# ab-main-mini.net
KiCad netlist of a schematic drawn in EAGLE
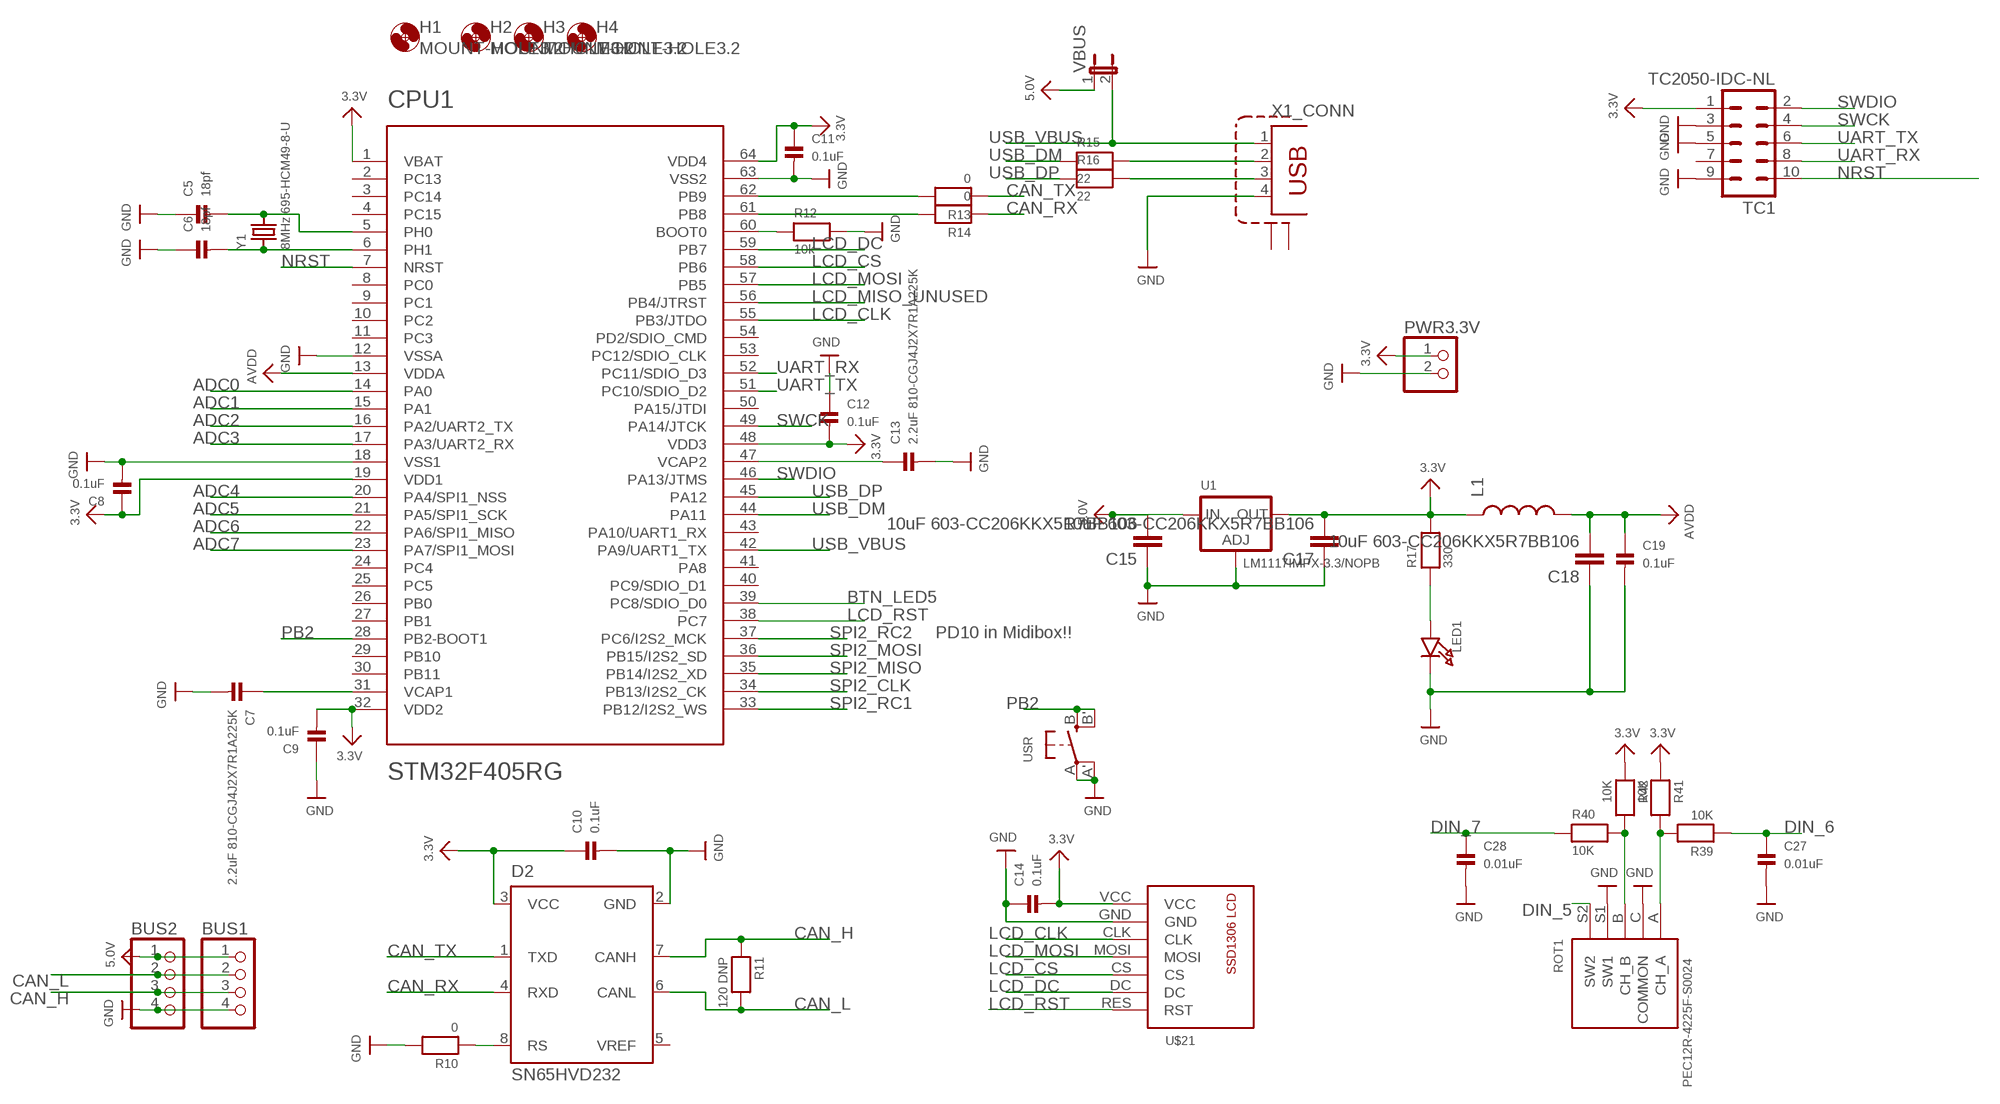
[diagram p0: schematic, sheet 1]

(export (version "E")
  (design (tool "Eeschema 10.0.6"))
  (components
    (comp (ref "BUS1")
      (value "HEADER-1X4ROUND")
      (footprint "eagle-import:1X04_ROUND")
      (libsource (lib "eagle-import") (part "HEADER-1X4ROUND"))
    )
    (comp (ref "BUS2")
      (value "HEADER-1X4ROUND")
      (footprint "eagle-import:1X04_ROUND")
      (libsource (lib "eagle-import") (part "HEADER-1X4ROUND"))
    )
    (comp (ref "C5")
      (value "18pf")
      (footprint "eagle-import:0603")
      (libsource (lib "eagle-import") (part "CAP_CERAMIC0603"))
    )
    (comp (ref "C6")
      (value "18pf")
      (footprint "eagle-import:0603")
      (libsource (lib "eagle-import") (part "CAP_CERAMIC0603"))
    )
    (comp (ref "C7")
      (value "2.2uF 810-CGJ4J2X7R1A225K")
      (footprint "eagle-import:0805")
      (libsource (lib "eagle-import") (part "CAP_CERAMIC0805"))
    )
    (comp (ref "C8")
      (value "0.1uF")
      (footprint "eagle-import:0603")
      (libsource (lib "eagle-import") (part "CAP_CERAMIC0603"))
    )
    (comp (ref "C9")
      (value "0.1uF")
      (footprint "eagle-import:0603")
      (libsource (lib "eagle-import") (part "CAP_CERAMIC0603"))
    )
    (comp (ref "C10")
      (value "0.1uF")
      (footprint "eagle-import:0603")
      (libsource (lib "eagle-import") (part "CAP_CERAMIC0603"))
    )
    (comp (ref "C11")
      (value "0.1uF")
      (footprint "eagle-import:0603")
      (libsource (lib "eagle-import") (part "CAP_CERAMIC0603"))
    )
    (comp (ref "C12")
      (value "0.1uF")
      (footprint "eagle-import:0603")
      (libsource (lib "eagle-import") (part "CAP_CERAMIC0603"))
    )
    (comp (ref "C13")
      (value "2.2uF 810-CGJ4J2X7R1A225K")
      (footprint "eagle-import:0805")
      (libsource (lib "eagle-import") (part "CAP_CERAMIC0805"))
    )
    (comp (ref "C14")
      (value "0.1uF")
      (footprint "eagle-import:0603")
      (libsource (lib "eagle-import") (part "CAP_CERAMIC0603"))
    )
    (comp (ref "C15")
      (value "10uF 603-CC206KKX5R7BB106")
      (footprint "eagle-import:1206")
      (libsource (lib "eagle-import") (part "CAP1206"))
    )
    (comp (ref "C17")
      (value "10uF 603-CC206KKX5R7BB106")
      (footprint "eagle-import:1206")
      (libsource (lib "eagle-import") (part "CAP1206"))
    )
    (comp (ref "C18")
      (value "10uF 603-CC206KKX5R7BB106")
      (footprint "eagle-import:1206")
      (libsource (lib "eagle-import") (part "CAP1206"))
    )
    (comp (ref "C19")
      (value "0.1uF")
      (footprint "eagle-import:0603")
      (libsource (lib "eagle-import") (part "CAP_CERAMIC0603"))
    )
    (comp (ref "C27")
      (value "0.01uF")
      (footprint "eagle-import:0603")
      (libsource (lib "eagle-import") (part "CAP_CERAMIC0603"))
    )
    (comp (ref "C28")
      (value "0.01uF")
      (footprint "eagle-import:0603")
      (libsource (lib "eagle-import") (part "CAP_CERAMIC0603"))
    )
    (comp (ref "CPU1")
      (value "STM32F405RG")
      (footprint "eagle-import:TQFP64")
      (libsource (lib "eagle-import") (part "STM32F405RG"))
    )
    (comp (ref "D2")
      (value "SN65HVD232")
      (footprint "eagle-import:SO8")
      (libsource (lib "eagle-import") (part "SN65HVD230"))
    )
    (comp (ref "H1")
      (value "MOUNT-HOLE3.2")
      (footprint "eagle-import:3,2")
      (libsource (lib "eagle-import") (part "MOUNT-HOLE3.2"))
    )
    (comp (ref "H2")
      (value "MOUNT-HOLE3.2")
      (footprint "eagle-import:3,2")
      (libsource (lib "eagle-import") (part "MOUNT-HOLE3.2"))
    )
    (comp (ref "H3")
      (value "MOUNT-HOLE3.2")
      (footprint "eagle-import:3,2")
      (libsource (lib "eagle-import") (part "MOUNT-HOLE3.2"))
    )
    (comp (ref "H4")
      (value "MOUNT-HOLE3.2")
      (footprint "eagle-import:3,2")
      (libsource (lib "eagle-import") (part "MOUNT-HOLE3.2"))
    )
    (comp (ref "L1")
      (value "INDUCTOR0805")
      (footprint "eagle-import:0805")
      (libsource (lib "eagle-import") (part "INDUCTOR0805"))
    )
    (comp (ref "LED1")
      (value "LED0603")
      (footprint "eagle-import:CHIPLED_0603")
      (libsource (lib "eagle-import") (part "LED0603"))
    )
    (comp (ref "PWR3.3V")
      (value "HEADER-1X2ROUND")
      (footprint "eagle-import:1X02_ROUND")
      (libsource (lib "eagle-import") (part "HEADER-1X2ROUND"))
    )
    (comp (ref "R10")
      (value "0")
      (footprint "eagle-import:_0603")
      (libsource (lib "eagle-import") (part "RESISTOR_0603"))
    )
    (comp (ref "R11")
      (value "120 DNP")
      (footprint "eagle-import:_0603")
      (libsource (lib "eagle-import") (part "RESISTOR_0603"))
    )
    (comp (ref "R12")
      (value "10k")
      (footprint "eagle-import:_0603")
      (libsource (lib "eagle-import") (part "RESISTOR_0603"))
    )
    (comp (ref "R13")
      (value "0")
      (footprint "eagle-import:_0603")
      (libsource (lib "eagle-import") (part "RESISTOR_0603"))
    )
    (comp (ref "R14")
      (value "0")
      (footprint "eagle-import:_0603")
      (libsource (lib "eagle-import") (part "RESISTOR_0603"))
    )
    (comp (ref "R15")
      (value "22")
      (footprint "eagle-import:0603")
      (libsource (lib "eagle-import") (part "RESISTOR0603"))
    )
    (comp (ref "R16")
      (value "22")
      (footprint "eagle-import:0603")
      (libsource (lib "eagle-import") (part "RESISTOR0603"))
    )
    (comp (ref "R17")
      (value "330")
      (footprint "eagle-import:0603")
      (libsource (lib "eagle-import") (part "RESISTOR0603"))
    )
    (comp (ref "R39")
      (value "10K")
      (footprint "eagle-import:0603")
      (libsource (lib "eagle-import") (part "RESISTOR0603"))
    )
    (comp (ref "R40")
      (value "10K")
      (footprint "eagle-import:0603")
      (libsource (lib "eagle-import") (part "RESISTOR0603"))
    )
    (comp (ref "R41")
      (value "10K")
      (footprint "eagle-import:0603")
      (libsource (lib "eagle-import") (part "RESISTOR0603"))
    )
    (comp (ref "R42")
      (value "10K")
      (footprint "eagle-import:0603")
      (libsource (lib "eagle-import") (part "RESISTOR0603"))
    )
    (comp (ref "ROT1")
      (value "PEC12R-4225F-S0024")
      (footprint "eagle-import:PEC111-4XXXK-SXXXX")
      (libsource (lib "eagle-import") (part "PEC11-4215K-S0024"))
    )
    (comp (ref "TC1")
      (value "TC2050-IDC-NL")
      (footprint "eagle-import:TC2050-IDC-NL")
      (libsource (lib "eagle-import") (part "TC2050-IDC-NL"))
    )
    (comp (ref "U$21")
      (value "SSD1306-7PIN")
      (footprint "eagle-import:SSD1306-7PIN")
      (libsource (lib "eagle-import") (part "SSD1306-7PIN"))
    )
    (comp (ref "U1")
      (value "LM1117IMPX-3.3/NOPB")
      (footprint "eagle-import:SOT223-R")
      (libsource (lib "eagle-import") (part "LM1117SOT223-REFLOW"))
    )
    (comp (ref "USR")
      (value "SWITCH_TACT_SMT")
      (footprint "eagle-import:EVQ-Q2")
      (libsource (lib "eagle-import") (part "SWITCH_TACT_SMT"))
    )
    (comp (ref "VBUS")
      (value "JUMPER2")
      (footprint "eagle-import:JUMPER2")
      (libsource (lib "eagle-import") (part "JUMPER2"))
    )
    (comp (ref "X1")
      (value "TE-292304-1")
      (footprint "eagle-import:TE-292304-1")
      (libsource (lib "eagle-import") (part "TE-292304-1"))
    )
    (comp (ref "Y1")
      (value "8MHz 695-HCM49-8-U")
      (footprint "eagle-import:HC49UP")
      (libsource (lib "eagle-import") (part "CRYSTALSMD"))
    )
  )
  (nets
    (net (code "1") (name "/ADC0") (class "Default")
      (node (ref "CPU1") (pin "14") (pinfunction "PA0_14") (pintype "bidirectional"))
    )
    (net (code "2") (name "/ADC1") (class "Default")
      (node (ref "CPU1") (pin "15") (pinfunction "PA1_15") (pintype "bidirectional"))
    )
    (net (code "3") (name "/ADC2") (class "Default")
      (node (ref "CPU1") (pin "16") (pinfunction "PA2/UART2_TX_16") (pintype "bidirectional"))
    )
    (net (code "4") (name "/ADC3") (class "Default")
      (node (ref "CPU1") (pin "17") (pinfunction "PA3/UART2_RX_17") (pintype "bidirectional"))
    )
    (net (code "5") (name "/ADC4") (class "Default")
      (node (ref "CPU1") (pin "20") (pinfunction "PA4/SPI1_NSS_20") (pintype "bidirectional"))
    )
    (net (code "6") (name "/ADC5") (class "Default")
      (node (ref "CPU1") (pin "21") (pinfunction "PA5/SPI1_SCK_21") (pintype "bidirectional"))
    )
    (net (code "7") (name "/ADC6") (class "Default")
      (node (ref "CPU1") (pin "22") (pinfunction "PA6/SPI1_MISO_22") (pintype "bidirectional"))
    )
    (net (code "8") (name "/ADC7") (class "Default")
      (node (ref "CPU1") (pin "23") (pinfunction "PA7/SPI1_MOSI_23") (pintype "bidirectional"))
    )
    (net (code "9") (name "/BTN_LED5") (class "Default")
      (node (ref "CPU1") (pin "39") (pinfunction "PC8/SDIO_D0_39") (pintype "bidirectional"))
    )
    (net (code "10") (name "/CAN_H") (class "Default")
      (node (ref "BUS1") (pin "3") (pinfunction "3_3") (pintype "passive"))
      (node (ref "BUS2") (pin "3") (pinfunction "3_3") (pintype "passive"))
      (node (ref "D2") (pin "7") (pinfunction "CANH_7") (pintype "bidirectional"))
      (node (ref "R11") (pin "1") (pinfunction "1_1") (pintype "passive"))
    )
    (net (code "11") (name "/CAN_L") (class "Default")
      (node (ref "BUS1") (pin "2") (pinfunction "2_2") (pintype "passive"))
      (node (ref "BUS2") (pin "2") (pinfunction "2_2") (pintype "passive"))
      (node (ref "D2") (pin "6") (pinfunction "CANL_6") (pintype "bidirectional"))
      (node (ref "R11") (pin "2") (pinfunction "2_2") (pintype "passive"))
    )
    (net (code "12") (name "/CAN_RX") (class "Default")
      (node (ref "D2") (pin "4") (pinfunction "RXD_4") (pintype "output"))
      (node (ref "R14") (pin "1") (pinfunction "1_1") (pintype "passive"))
    )
    (net (code "13") (name "/CAN_TX") (class "Default")
      (node (ref "D2") (pin "1") (pinfunction "TXD_1") (pintype "input"))
      (node (ref "R13") (pin "1") (pinfunction "1_1") (pintype "passive"))
    )
    (net (code "14") (name "/DIN_5") (class "Default")
      (node (ref "ROT1") (pin "S2") (pinfunction "SW2_S2") (pintype "bidirectional"))
    )
    (net (code "15") (name "/DIN_6") (class "Default")
      (node (ref "C27") (pin "1") (pinfunction "P$1_1") (pintype "passive"))
      (node (ref "R39") (pin "1") (pinfunction "1_1") (pintype "passive"))
    )
    (net (code "16") (name "/DIN_7") (class "Default")
      (node (ref "C28") (pin "1") (pinfunction "P$1_1") (pintype "passive"))
      (node (ref "R40") (pin "1") (pinfunction "1_1") (pintype "passive"))
    )
    (net (code "17") (name "/LCD_CLK") (class "Default")
      (node (ref "CPU1") (pin "55") (pinfunction "PB3/JTDO_55") (pintype "bidirectional"))
      (node (ref "U$21") (pin "CLK") (pinfunction "CLK_CLK") (pintype "bidirectional"))
    )
    (net (code "18") (name "/LCD_CS") (class "Default")
      (node (ref "CPU1") (pin "58") (pinfunction "PB6_58") (pintype "bidirectional"))
      (node (ref "U$21") (pin "CS") (pinfunction "CS_CS") (pintype "bidirectional"))
    )
    (net (code "19") (name "/LCD_DC") (class "Default")
      (node (ref "CPU1") (pin "59") (pinfunction "PB7_59") (pintype "bidirectional"))
      (node (ref "U$21") (pin "DC") (pinfunction "DC_DC") (pintype "bidirectional"))
    )
    (net (code "20") (name "/LCD_MISO_UNUSED") (class "Default")
      (node (ref "CPU1") (pin "56") (pinfunction "PB4/JTRST_56") (pintype "bidirectional"))
    )
    (net (code "21") (name "/LCD_MOSI") (class "Default")
      (node (ref "CPU1") (pin "57") (pinfunction "PB5_57") (pintype "bidirectional"))
      (node (ref "U$21") (pin "MOSI") (pinfunction "MOSI_MOSI") (pintype "bidirectional"))
    )
    (net (code "22") (name "/LCD_RST") (class "Default")
      (node (ref "CPU1") (pin "38") (pinfunction "PC7_38") (pintype "bidirectional"))
      (node (ref "U$21") (pin "RES") (pinfunction "RST_RES") (pintype "bidirectional"))
    )
    (net (code "23") (name "/NRST") (class "Default")
      (node (ref "CPU1") (pin "7") (pinfunction "NRST_7") (pintype "bidirectional"))
      (node (ref "TC1") (pin "10") (pinfunction "10_10") (pintype "passive"))
    )
    (net (code "24") (name "/PB2") (class "Default")
      (node (ref "CPU1") (pin "28") (pinfunction "PB2-BOOT1_28") (pintype "bidirectional"))
      (node (ref "USR") (pin "B") (pinfunction "S_B") (pintype "passive"))
      (node (ref "USR") (pin "B'") (pinfunction "S1_B'") (pintype "passive"))
    )
    (net (code "25") (name "/SPI2_CLK") (class "Default")
      (node (ref "CPU1") (pin "34") (pinfunction "PB13/I2S2_CK_34") (pintype "bidirectional"))
    )
    (net (code "26") (name "/SPI2_MISO") (class "Default")
      (node (ref "CPU1") (pin "35") (pinfunction "PB14/I2S2_XD_35") (pintype "bidirectional"))
    )
    (net (code "27") (name "/SPI2_MOSI") (class "Default")
      (node (ref "CPU1") (pin "36") (pinfunction "PB15/I2S2_SD_36") (pintype "bidirectional"))
    )
    (net (code "28") (name "/SPI2_RC1") (class "Default")
      (node (ref "CPU1") (pin "33") (pinfunction "PB12/I2S2_WS_33") (pintype "bidirectional"))
    )
    (net (code "29") (name "/SPI2_RC2") (class "Default")
      (node (ref "CPU1") (pin "37") (pinfunction "PC6/I2S2_MCK_37") (pintype "bidirectional"))
    )
    (net (code "30") (name "/SWCK") (class "Default")
      (node (ref "CPU1") (pin "49") (pinfunction "PA14/JTCK_49") (pintype "bidirectional"))
      (node (ref "TC1") (pin "4") (pinfunction "4_4") (pintype "passive"))
    )
    (net (code "31") (name "/SWDIO") (class "Default")
      (node (ref "CPU1") (pin "46") (pinfunction "PA13/JTMS_46") (pintype "bidirectional"))
      (node (ref "TC1") (pin "2") (pinfunction "2_2") (pintype "passive"))
    )
    (net (code "32") (name "/UART_RX") (class "Default")
      (node (ref "CPU1") (pin "52") (pinfunction "PC11/SDIO_D3_52") (pintype "bidirectional"))
      (node (ref "TC1") (pin "8") (pinfunction "8_8") (pintype "passive"))
    )
    (net (code "33") (name "/UART_TX") (class "Default")
      (node (ref "CPU1") (pin "51") (pinfunction "PC10/SDIO_D2_51") (pintype "bidirectional"))
      (node (ref "TC1") (pin "6") (pinfunction "6_6") (pintype "passive"))
    )
    (net (code "34") (name "/USB_DM") (class "Default")
      (node (ref "CPU1") (pin "44") (pinfunction "PA11_44") (pintype "bidirectional"))
      (node (ref "R15") (pin "1") (pinfunction "1_1") (pintype "passive"))
    )
    (net (code "35") (name "/USB_DP") (class "Default")
      (node (ref "CPU1") (pin "45") (pinfunction "PA12_45") (pintype "bidirectional"))
      (node (ref "R16") (pin "1") (pinfunction "1_1") (pintype "passive"))
    )
    (net (code "36") (name "/USB_VBUS") (class "Default")
      (node (ref "CPU1") (pin "42") (pinfunction "PA9/UART1_TX_42") (pintype "bidirectional"))
      (node (ref "VBUS") (pin "2") (pinfunction "2_2") (pintype "passive"))
      (node (ref "X1") (pin "1") (pinfunction "1_1") (pintype "bidirectional"))
    )
    (net (code "37") (name "3.3V") (class "Default")
      (node (ref "C10") (pin "1") (pinfunction "P$1_1") (pintype "passive"))
      (node (ref "C11") (pin "1") (pinfunction "P$1_1") (pintype "passive"))
      (node (ref "C12") (pin "2") (pinfunction "P$2_2") (pintype "passive"))
      (node (ref "C14") (pin "2") (pinfunction "P$2_2") (pintype "passive"))
      (node (ref "C17") (pin "2") (pinfunction "2_2") (pintype "passive"))
      (node (ref "C8") (pin "1") (pinfunction "P$1_1") (pintype "passive"))
      (node (ref "C9") (pin "2") (pinfunction "P$2_2") (pintype "passive"))
      (node (ref "CPU1") (pin "1") (pinfunction "VBAT_1") (pintype "bidirectional"))
      (node (ref "CPU1") (pin "19") (pinfunction "VDD1_19") (pintype "bidirectional"))
      (node (ref "CPU1") (pin "32") (pinfunction "VDD2_32") (pintype "bidirectional"))
      (node (ref "CPU1") (pin "48") (pinfunction "VDD3_48") (pintype "bidirectional"))
      (node (ref "CPU1") (pin "64") (pinfunction "VDD4_64") (pintype "bidirectional"))
      (node (ref "D2") (pin "3") (pinfunction "VCC_3") (pintype "power_in"))
      (node (ref "L1") (pin "1") (pinfunction "1_1") (pintype "passive"))
      (node (ref "PWR3.3V") (pin "1") (pinfunction "1_1") (pintype "passive"))
      (node (ref "R17") (pin "2") (pinfunction "2_2") (pintype "passive"))
      (node (ref "R41") (pin "1") (pinfunction "1_1") (pintype "passive"))
      (node (ref "R42") (pin "1") (pinfunction "1_1") (pintype "passive"))
      (node (ref "TC1") (pin "1") (pinfunction "1_1") (pintype "passive"))
      (node (ref "U$21") (pin "VCC") (pinfunction "VCC_VCC") (pintype "bidirectional"))
      (node (ref "U1") (pin "2") (pinfunction "OUT_2") (pintype "passive"))
    )
    (net (code "38") (name "5.0V") (class "Default")
      (node (ref "BUS1") (pin "1") (pinfunction "1_1") (pintype "passive"))
      (node (ref "BUS2") (pin "1") (pinfunction "1_1") (pintype "passive"))
      (node (ref "C15") (pin "2") (pinfunction "2_2") (pintype "passive"))
      (node (ref "U1") (pin "3") (pinfunction "IN_3") (pintype "input"))
      (node (ref "VBUS") (pin "1") (pinfunction "1_1") (pintype "passive"))
    )
    (net (code "39") (name "AVDD") (class "Default")
      (node (ref "C18") (pin "2") (pinfunction "2_2") (pintype "passive"))
      (node (ref "C19") (pin "1") (pinfunction "P$1_1") (pintype "passive"))
      (node (ref "CPU1") (pin "13") (pinfunction "VDDA_13") (pintype "bidirectional"))
      (node (ref "L1") (pin "2") (pinfunction "2_2") (pintype "passive"))
    )
    (net (code "40") (name "GND") (class "Default")
      (node (ref "BUS1") (pin "4") (pinfunction "4_4") (pintype "passive"))
      (node (ref "BUS2") (pin "4") (pinfunction "4_4") (pintype "passive"))
      (node (ref "C10") (pin "2") (pinfunction "P$2_2") (pintype "passive"))
      (node (ref "C11") (pin "2") (pinfunction "P$2_2") (pintype "passive"))
      (node (ref "C12") (pin "1") (pinfunction "P$1_1") (pintype "passive"))
      (node (ref "C13") (pin "2") (pinfunction "P$2_2") (pintype "passive"))
      (node (ref "C14") (pin "1") (pinfunction "P$1_1") (pintype "passive"))
      (node (ref "C15") (pin "1") (pinfunction "1_1") (pintype "passive"))
      (node (ref "C17") (pin "1") (pinfunction "1_1") (pintype "passive"))
      (node (ref "C18") (pin "1") (pinfunction "1_1") (pintype "passive"))
      (node (ref "C19") (pin "2") (pinfunction "P$2_2") (pintype "passive"))
      (node (ref "C27") (pin "2") (pinfunction "P$2_2") (pintype "passive"))
      (node (ref "C28") (pin "2") (pinfunction "P$2_2") (pintype "passive"))
      (node (ref "C5") (pin "1") (pinfunction "P$1_1") (pintype "passive"))
      (node (ref "C6") (pin "1") (pinfunction "P$1_1") (pintype "passive"))
      (node (ref "C7") (pin "2") (pinfunction "P$2_2") (pintype "passive"))
      (node (ref "C8") (pin "2") (pinfunction "P$2_2") (pintype "passive"))
      (node (ref "C9") (pin "1") (pinfunction "P$1_1") (pintype "passive"))
      (node (ref "CPU1") (pin "12") (pinfunction "VSSA_12") (pintype "bidirectional"))
      (node (ref "CPU1") (pin "18") (pinfunction "VSS1_18") (pintype "bidirectional"))
      (node (ref "CPU1") (pin "63") (pinfunction "VSS2_63") (pintype "bidirectional"))
      (node (ref "D2") (pin "2") (pinfunction "GND_2") (pintype "power_in"))
      (node (ref "LED1") (pin "C") (pinfunction "C_C") (pintype "passive"))
      (node (ref "PWR3.3V") (pin "2") (pinfunction "2_2") (pintype "passive"))
      (node (ref "R10") (pin "2") (pinfunction "2_2") (pintype "passive"))
      (node (ref "R12") (pin "2") (pinfunction "2_2") (pintype "passive"))
      (node (ref "ROT1") (pin "C") (pinfunction "COMMON_C") (pintype "input"))
      (node (ref "ROT1") (pin "S1") (pinfunction "SW1_S1") (pintype "bidirectional"))
      (node (ref "TC1") (pin "3") (pinfunction "3_3") (pintype "passive"))
      (node (ref "TC1") (pin "5") (pinfunction "5_5") (pintype "passive"))
      (node (ref "TC1") (pin "9") (pinfunction "9_9") (pintype "passive"))
      (node (ref "U$21") (pin "GND") (pinfunction "GND_GND") (pintype "bidirectional"))
      (node (ref "U1") (pin "1") (pinfunction "ADJ_1") (pintype "input"))
      (node (ref "USR") (pin "A") (pinfunction "P_A") (pintype "passive"))
      (node (ref "USR") (pin "A'") (pinfunction "P1_A'") (pintype "passive"))
      (node (ref "X1") (pin "4") (pinfunction "4_4") (pintype "bidirectional"))
    )
    (net (code "41") (name "Net-(C5-P$2)") (class "Default")
      (node (ref "C5") (pin "2") (pinfunction "P$2_2") (pintype "passive"))
      (node (ref "CPU1") (pin "5") (pinfunction "PH0_5") (pintype "bidirectional"))
      (node (ref "Y1") (pin "2") (pinfunction "2_2") (pintype "passive"))
    )
    (net (code "42") (name "Net-(C6-P$2)") (class "Default")
      (node (ref "C6") (pin "2") (pinfunction "P$2_2") (pintype "passive"))
      (node (ref "CPU1") (pin "6") (pinfunction "PH1_6") (pintype "bidirectional"))
      (node (ref "Y1") (pin "1") (pinfunction "1_1") (pintype "passive"))
    )
    (net (code "43") (name "Net-(C7-P$1)") (class "Default")
      (node (ref "C7") (pin "1") (pinfunction "P$1_1") (pintype "passive"))
      (node (ref "CPU1") (pin "31") (pinfunction "VCAP1_31") (pintype "bidirectional"))
    )
    (net (code "44") (name "Net-(C13-P$1)") (class "Default")
      (node (ref "C13") (pin "1") (pinfunction "P$1_1") (pintype "passive"))
      (node (ref "CPU1") (pin "47") (pinfunction "VCAP2_47") (pintype "bidirectional"))
    )
    (net (code "45") (name "Net-(CPU1-BOOT0)") (class "Default")
      (node (ref "CPU1") (pin "60") (pinfunction "BOOT0_60") (pintype "bidirectional"))
      (node (ref "R12") (pin "1") (pinfunction "1_1") (pintype "passive"))
    )
    (net (code "46") (name "Net-(CPU1-PB8)") (class "Default")
      (node (ref "CPU1") (pin "61") (pinfunction "PB8_61") (pintype "bidirectional"))
      (node (ref "R14") (pin "2") (pinfunction "2_2") (pintype "passive"))
    )
    (net (code "47") (name "Net-(CPU1-PB9)") (class "Default")
      (node (ref "CPU1") (pin "62") (pinfunction "PB9_62") (pintype "bidirectional"))
      (node (ref "R13") (pin "2") (pinfunction "2_2") (pintype "passive"))
    )
    (net (code "48") (name "Net-(D2-RS)") (class "Default")
      (node (ref "D2") (pin "8") (pinfunction "RS_8") (pintype "input"))
      (node (ref "R10") (pin "1") (pinfunction "1_1") (pintype "passive"))
    )
    (net (code "49") (name "Net-(LED1-PadA)") (class "Default")
      (node (ref "LED1") (pin "A") (pinfunction "A_A") (pintype "passive"))
      (node (ref "R17") (pin "1") (pinfunction "1_1") (pintype "passive"))
    )
    (net (code "50") (name "Net-(R15-Pad2)") (class "Default")
      (node (ref "R15") (pin "2") (pinfunction "2_2") (pintype "passive"))
      (node (ref "X1") (pin "2") (pinfunction "2_2") (pintype "bidirectional"))
    )
    (net (code "51") (name "Net-(R16-Pad2)") (class "Default")
      (node (ref "R16") (pin "2") (pinfunction "2_2") (pintype "passive"))
      (node (ref "X1") (pin "3") (pinfunction "3_3") (pintype "bidirectional"))
    )
    (net (code "52") (name "Net-(ROT1-CH_A)") (class "Default")
      (node (ref "R39") (pin "2") (pinfunction "2_2") (pintype "passive"))
      (node (ref "R41") (pin "2") (pinfunction "2_2") (pintype "passive"))
      (node (ref "ROT1") (pin "A") (pinfunction "CH_A_A") (pintype "output"))
    )
    (net (code "53") (name "Net-(ROT1-CH_B)") (class "Default")
      (node (ref "R40") (pin "2") (pinfunction "2_2") (pintype "passive"))
      (node (ref "R42") (pin "2") (pinfunction "2_2") (pintype "passive"))
      (node (ref "ROT1") (pin "B") (pinfunction "CH_B_B") (pintype "output"))
    )
    (net (code "54") (name "unconnected-(CPU1-PA8-Pad41)") (class "Default")
      (node (ref "CPU1") (pin "41") (pinfunction "PA8_41") (pintype "bidirectional"))
    )
    (net (code "55") (name "unconnected-(CPU1-PA10{slash}UART1_RX-Pad43)") (class "Default")
      (node (ref "CPU1") (pin "43") (pinfunction "PA10/UART1_RX_43") (pintype "bidirectional"))
    )
    (net (code "56") (name "unconnected-(CPU1-PA15{slash}JTDI-Pad50)") (class "Default")
      (node (ref "CPU1") (pin "50") (pinfunction "PA15/JTDI_50") (pintype "bidirectional"))
    )
    (net (code "57") (name "unconnected-(CPU1-PB0-Pad26)") (class "Default")
      (node (ref "CPU1") (pin "26") (pinfunction "PB0_26") (pintype "bidirectional"))
    )
    (net (code "58") (name "unconnected-(CPU1-PB1-Pad27)") (class "Default")
      (node (ref "CPU1") (pin "27") (pinfunction "PB1_27") (pintype "bidirectional"))
    )
    (net (code "59") (name "unconnected-(CPU1-PB10-Pad29)") (class "Default")
      (node (ref "CPU1") (pin "29") (pinfunction "PB10_29") (pintype "bidirectional"))
    )
    (net (code "60") (name "unconnected-(CPU1-PB11-Pad30)") (class "Default")
      (node (ref "CPU1") (pin "30") (pinfunction "PB11_30") (pintype "bidirectional"))
    )
    (net (code "61") (name "unconnected-(CPU1-PC0-Pad8)") (class "Default")
      (node (ref "CPU1") (pin "8") (pinfunction "PC0_8") (pintype "bidirectional"))
    )
    (net (code "62") (name "unconnected-(CPU1-PC1-Pad9)") (class "Default")
      (node (ref "CPU1") (pin "9") (pinfunction "PC1_9") (pintype "bidirectional"))
    )
    (net (code "63") (name "unconnected-(CPU1-PC2-Pad10)") (class "Default")
      (node (ref "CPU1") (pin "10") (pinfunction "PC2_10") (pintype "bidirectional"))
    )
    (net (code "64") (name "unconnected-(CPU1-PC3-Pad11)") (class "Default")
      (node (ref "CPU1") (pin "11") (pinfunction "PC3_11") (pintype "bidirectional"))
    )
    (net (code "65") (name "unconnected-(CPU1-PC4-Pad24)") (class "Default")
      (node (ref "CPU1") (pin "24") (pinfunction "PC4_24") (pintype "bidirectional"))
    )
    (net (code "66") (name "unconnected-(CPU1-PC5-Pad25)") (class "Default")
      (node (ref "CPU1") (pin "25") (pinfunction "PC5_25") (pintype "bidirectional"))
    )
    (net (code "67") (name "unconnected-(CPU1-PC9{slash}SDIO_D1-Pad40)") (class "Default")
      (node (ref "CPU1") (pin "40") (pinfunction "PC9/SDIO_D1_40") (pintype "bidirectional"))
    )
    (net (code "68") (name "unconnected-(CPU1-PC12{slash}SDIO_CLK-Pad53)") (class "Default")
      (node (ref "CPU1") (pin "53") (pinfunction "PC12/SDIO_CLK_53") (pintype "bidirectional"))
    )
    (net (code "69") (name "unconnected-(CPU1-PC13-Pad2)") (class "Default")
      (node (ref "CPU1") (pin "2") (pinfunction "PC13_2") (pintype "bidirectional"))
    )
    (net (code "70") (name "unconnected-(CPU1-PC14-Pad3)") (class "Default")
      (node (ref "CPU1") (pin "3") (pinfunction "PC14_3") (pintype "bidirectional"))
    )
    (net (code "71") (name "unconnected-(CPU1-PC15-Pad4)") (class "Default")
      (node (ref "CPU1") (pin "4") (pinfunction "PC15_4") (pintype "bidirectional"))
    )
    (net (code "72") (name "unconnected-(CPU1-PD2{slash}SDIO_CMD-Pad54)") (class "Default")
      (node (ref "CPU1") (pin "54") (pinfunction "PD2/SDIO_CMD_54") (pintype "bidirectional"))
    )
    (net (code "73") (name "unconnected-(D2-VREF-Pad5)") (class "Default")
      (node (ref "D2") (pin "5") (pinfunction "VREF_5") (pintype "output"))
    )
    (net (code "74") (name "unconnected-(TC1-Pad7)") (class "Default")
      (node (ref "TC1") (pin "7") (pinfunction "7_7") (pintype "passive"))
    )
    (net (code "75") (name "unconnected-(X1A-S1-PadP$1)") (class "Default")
      (node (ref "X1") (pin "P$1") (pinfunction "S1_P$1") (pintype "passive"))
    )
    (net (code "76") (name "unconnected-(X1A-S2-PadP$2)") (class "Default")
      (node (ref "X1") (pin "P$2") (pinfunction "S2_P$2") (pintype "passive"))
    )
  )
)
